# Codec.net
KiCad netlist of a schematic drawn in Altium Designer
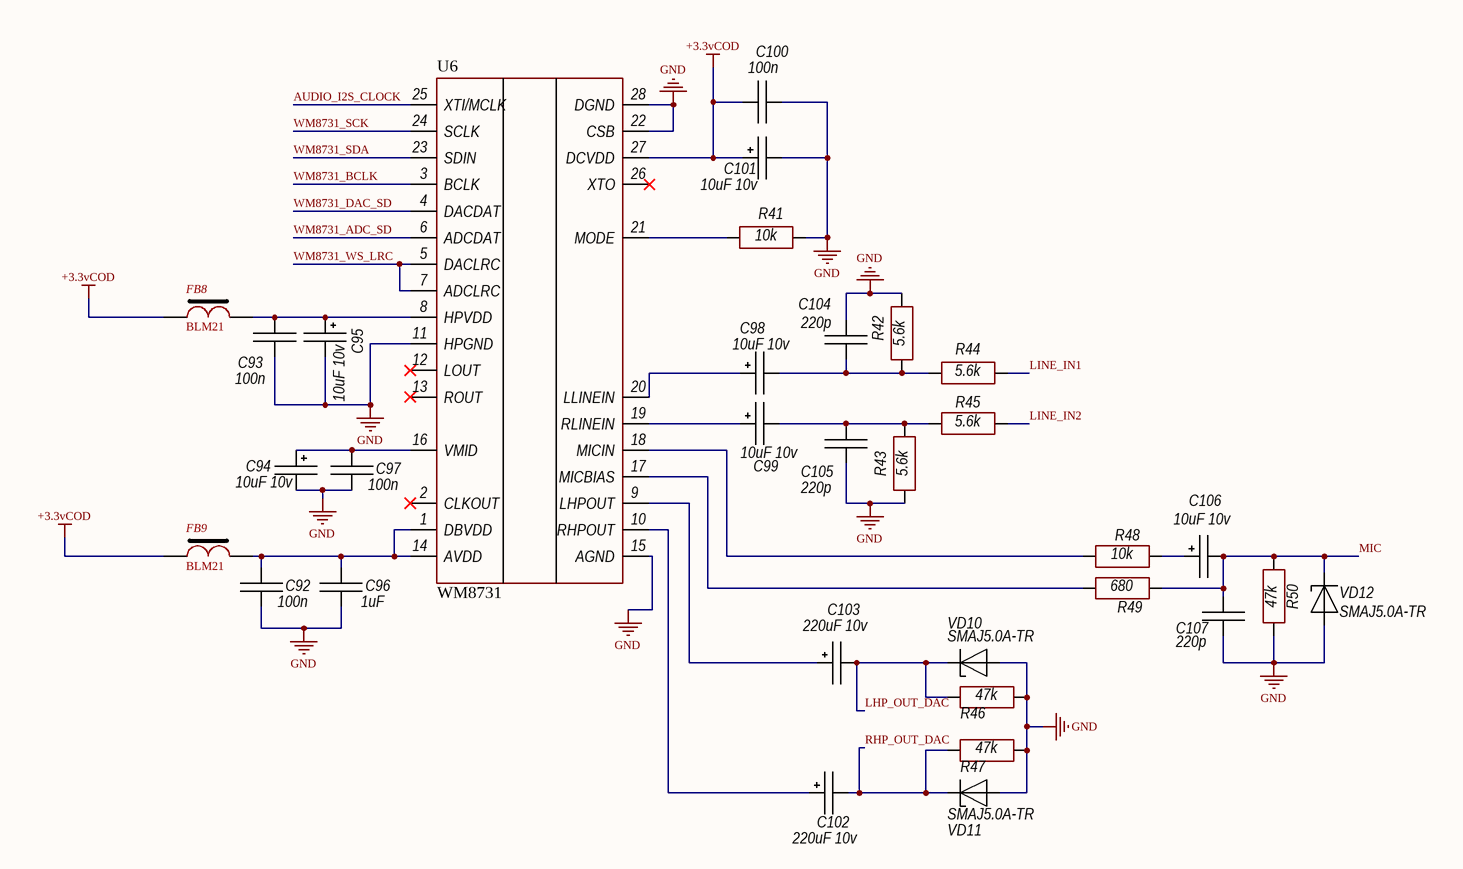
[diagram p0: Codec.SchDoc]

(export (version "E")
  (design (tool "Eeschema 10.0.6"))
  (components
    (comp (ref "C92")
      (value "100n")
      (footprint "standard:CH0805C")
      (libsource (lib "Discrete") (part "Capacitor"))
    )
    (comp (ref "C93")
      (value "100n")
      (footprint "standard:CH0805C")
      (libsource (lib "Discrete") (part "Capacitor"))
    )
    (comp (ref "C94")
      (value "10uF 10v")
      (footprint "standard:TANTAL_B")
      (libsource (lib "Discrete") (part "TantalCap"))
    )
    (comp (ref "C95")
      (value "10uF 10v")
      (footprint "standard:TANTAL_B")
      (libsource (lib "Discrete") (part "TantalCap"))
    )
    (comp (ref "C96")
      (value "1uF")
      (footprint "standard:CH0805C")
      (libsource (lib "Discrete") (part "Capacitor"))
    )
    (comp (ref "C97")
      (value "100n")
      (footprint "standard:CH0805C")
      (libsource (lib "Discrete") (part "Capacitor"))
    )
    (comp (ref "C98")
      (value "10uF 10v")
      (footprint "standard:TANTAL_B")
      (libsource (lib "Discrete") (part "TantalCap"))
    )
    (comp (ref "C99")
      (value "10uF 10v")
      (footprint "standard:TANTAL_B")
      (libsource (lib "Discrete") (part "TantalCap"))
    )
    (comp (ref "C100")
      (value "100n")
      (footprint "standard:CH0805C")
      (libsource (lib "Discrete") (part "Capacitor"))
    )
    (comp (ref "C101")
      (value "10uF 10v")
      (footprint "standard:TANTAL_B")
      (libsource (lib "Discrete") (part "TantalCap"))
    )
    (comp (ref "C102")
      (value "220uF 10v")
      (footprint "standard:TANTAL_D")
      (libsource (lib "Discrete") (part "TantalCap"))
    )
    (comp (ref "C103")
      (value "220uF 10v")
      (footprint "standard:TANTAL_D")
      (libsource (lib "Discrete") (part "TantalCap"))
    )
    (comp (ref "C104")
      (value "220p")
      (footprint "standard:CH0805C")
      (libsource (lib "Discrete") (part "Capacitor"))
    )
    (comp (ref "C105")
      (value "220p")
      (footprint "standard:CH0805C")
      (libsource (lib "Discrete") (part "Capacitor"))
    )
    (comp (ref "C106")
      (value "10uF 10v")
      (footprint "standard:TANTAL_B")
      (libsource (lib "Discrete") (part "TantalCap"))
    )
    (comp (ref "C107")
      (value "220p")
      (footprint "standard:CH0805C")
      (libsource (lib "Discrete") (part "Capacitor"))
    )
    (comp (ref "FB8") (value "BLM21") (footprint "CH0805L") (libsource (lib "Discrete") (part "FB-1")))
    (comp (ref "FB9") (value "BLM21") (footprint "CH0805L") (libsource (lib "Discrete") (part "FB-1")))
    (comp (ref "R41")
      (value "10k")
      (footprint "standard:CH0805R")
      (libsource (lib "Discrete") (part "Resistor"))
    )
    (comp (ref "R42") (value "5.6k") (footprint "standard:CH0805R") (libsource (lib "") (part "Resistor_1")))
    (comp (ref "R43") (value "5.6k") (footprint "standard:CH0805R") (libsource (lib "") (part "Resistor_1")))
    (comp (ref "R44") (value "5.6k") (footprint "standard:CH0805R") (libsource (lib "") (part "Resistor_2")))
    (comp (ref "R45") (value "5.6k") (footprint "standard:CH0805R") (libsource (lib "") (part "Resistor_2")))
    (comp (ref "R46")
      (value "47k")
      (footprint "standard:CH0805R")
      (libsource (lib "Discrete") (part "Resistor"))
    )
    (comp (ref "R47")
      (value "47k")
      (footprint "standard:CH0805R")
      (libsource (lib "Discrete") (part "Resistor"))
    )
    (comp (ref "R48")
      (value "10k")
      (footprint "standard:CH0805R")
      (libsource (lib "Discrete") (part "Resistor"))
    )
    (comp (ref "R49")
      (value "680")
      (footprint "standard:CH0805R")
      (libsource (lib "Discrete") (part "Resistor"))
    )
    (comp (ref "R50") (value "47k") (footprint "standard:CH0805R") (libsource (lib "") (part "Resistor_1")))
    (comp (ref "U6") (value "WM8731") (footprint "28-SSOP") (libsource (lib "Digital") (part "WM8731")))
    (comp (ref "VD10")
      (value "SMAJ5.0A-TR")
      (footprint "standard:SMA")
      (libsource (lib "Diods") (part "Diod Zener"))
    )
    (comp (ref "VD11")
      (value "SMAJ5.0A-TR")
      (footprint "standard:SMA")
      (libsource (lib "Diods") (part "Diod Zener"))
    )
    (comp (ref "VD12")
      (value "SMAJ5.0A-TR")
      (footprint "standard:SMA")
      (libsource (lib "Diods") (part "Diod Zener"))
    )
  )
  (nets
    (net (code "1") (name "+3.3vCOD") (class "Default")
      (node (ref "C100") (pin "1") (pinfunction "1_1") (pintype "power_in"))
      (node (ref "C101") (pin "1") (pinfunction "1_1") (pintype "power_in"))
      (node (ref "FB8") (pin "2") (pinfunction "2_2") (pintype "passive"))
      (node (ref "FB9") (pin "2") (pinfunction "2_2") (pintype "passive"))
      (node (ref "U6") (pin "27") (pinfunction "DCVDD_27") (pintype "passive"))
    )
    (net (code "2") (name "/AUDIO_I2S_CLOCK") (class "Default")
      (node (ref "U6") (pin "25") (pinfunction "XTI/MCLK_25") (pintype "passive"))
    )
    (net (code "3") (name "/LHP_OUT_DAC") (class "Default")
      (node (ref "C103") (pin "2") (pinfunction "2_2") (pintype "power_in"))
      (node (ref "R46") (pin "1") (pinfunction "1_1") (pintype "passive"))
      (node (ref "VD10") (pin "2") (pinfunction "C_2") (pintype "passive"))
    )
    (net (code "4") (name "/LINE_IN1") (class "Default")
      (node (ref "R44") (pin "2") (pinfunction "2_2") (pintype "passive"))
    )
    (net (code "5") (name "/LINE_IN2") (class "Default")
      (node (ref "R45") (pin "2") (pinfunction "2_2") (pintype "passive"))
    )
    (net (code "6") (name "/MIC") (class "Default")
      (node (ref "C106") (pin "2") (pinfunction "2_2") (pintype "power_in"))
      (node (ref "C107") (pin "1") (pinfunction "1_1") (pintype "power_in"))
      (node (ref "R49") (pin "2") (pinfunction "2_2") (pintype "passive"))
      (node (ref "R50") (pin "2") (pinfunction "2_2") (pintype "passive"))
      (node (ref "VD12") (pin "2") (pinfunction "C_2") (pintype "passive"))
    )
    (net (code "7") (name "/RHP_OUT_DAC") (class "Default")
      (node (ref "C102") (pin "2") (pinfunction "2_2") (pintype "power_in"))
      (node (ref "R47") (pin "1") (pinfunction "1_1") (pintype "passive"))
      (node (ref "VD11") (pin "2") (pinfunction "C_2") (pintype "passive"))
    )
    (net (code "8") (name "/WM8731_ADC_SD") (class "Default")
      (node (ref "U6") (pin "6") (pinfunction "ADCDAT_6") (pintype "passive"))
    )
    (net (code "9") (name "/WM8731_BCLK") (class "Default")
      (node (ref "U6") (pin "3") (pinfunction "BCLK_3") (pintype "passive"))
    )
    (net (code "10") (name "/WM8731_DAC_SD") (class "Default")
      (node (ref "U6") (pin "4") (pinfunction "DACDAT_4") (pintype "passive"))
    )
    (net (code "11") (name "/WM8731_SCK") (class "Default")
      (node (ref "U6") (pin "24") (pinfunction "SCLK_24") (pintype "passive"))
    )
    (net (code "12") (name "/WM8731_SDA") (class "Default")
      (node (ref "U6") (pin "23") (pinfunction "SDIN_23") (pintype "passive"))
    )
    (net (code "13") (name "/WM8731_WS_LRC") (class "Default")
      (node (ref "U6") (pin "5") (pinfunction "DACLRC_5") (pintype "passive"))
      (node (ref "U6") (pin "7") (pinfunction "ADCLRC_7") (pintype "passive"))
    )
    (net (code "14") (name "GND") (class "Default")
      (node (ref "C100") (pin "2") (pinfunction "2_2") (pintype "power_in"))
      (node (ref "C101") (pin "2") (pinfunction "2_2") (pintype "power_in"))
      (node (ref "C104") (pin "2") (pinfunction "2_2") (pintype "power_in"))
      (node (ref "C105") (pin "1") (pinfunction "1_1") (pintype "power_in"))
      (node (ref "C107") (pin "2") (pinfunction "2_2") (pintype "power_in"))
      (node (ref "C92") (pin "1") (pinfunction "1_1") (pintype "power_in"))
      (node (ref "C93") (pin "1") (pinfunction "1_1") (pintype "power_in"))
      (node (ref "C94") (pin "2") (pinfunction "2_2") (pintype "power_in"))
      (node (ref "C95") (pin "2") (pinfunction "2_2") (pintype "power_in"))
      (node (ref "C96") (pin "1") (pinfunction "1_1") (pintype "power_in"))
      (node (ref "C97") (pin "1") (pinfunction "1_1") (pintype "power_in"))
      (node (ref "R41") (pin "2") (pinfunction "2_2") (pintype "passive"))
      (node (ref "R42") (pin "2") (pinfunction "2_2") (pintype "passive"))
      (node (ref "R43") (pin "1") (pinfunction "1_1") (pintype "passive"))
      (node (ref "R46") (pin "2") (pinfunction "2_2") (pintype "passive"))
      (node (ref "R47") (pin "2") (pinfunction "2_2") (pintype "passive"))
      (node (ref "R50") (pin "1") (pinfunction "1_1") (pintype "passive"))
      (node (ref "U6") (pin "11") (pinfunction "HPGND_11") (pintype "passive"))
      (node (ref "U6") (pin "15") (pinfunction "AGND_15") (pintype "passive"))
      (node (ref "U6") (pin "22") (pinfunction "CSB_22") (pintype "passive"))
      (node (ref "U6") (pin "28") (pinfunction "DGND_28") (pintype "passive"))
      (node (ref "VD10") (pin "1") (pinfunction "A_1") (pintype "passive"))
      (node (ref "VD11") (pin "1") (pinfunction "A_1") (pintype "passive"))
      (node (ref "VD12") (pin "1") (pinfunction "A_1") (pintype "passive"))
    )
    (net (code "15") (name "Net-(C104-Pad1)") (class "Default")
      (node (ref "C104") (pin "1") (pinfunction "1_1") (pintype "power_in"))
      (node (ref "C98") (pin "2") (pinfunction "2_2") (pintype "power_in"))
      (node (ref "R42") (pin "1") (pinfunction "1_1") (pintype "passive"))
      (node (ref "R44") (pin "1") (pinfunction "1_1") (pintype "passive"))
    )
    (net (code "16") (name "Net-(C105-Pad2)") (class "Default")
      (node (ref "C105") (pin "2") (pinfunction "2_2") (pintype "power_in"))
      (node (ref "C99") (pin "2") (pinfunction "2_2") (pintype "power_in"))
      (node (ref "R43") (pin "2") (pinfunction "2_2") (pintype "passive"))
      (node (ref "R45") (pin "1") (pinfunction "1_1") (pintype "passive"))
    )
    (net (code "17") (name "Net-(C106-Pad1)") (class "Default")
      (node (ref "C106") (pin "1") (pinfunction "1_1") (pintype "power_in"))
      (node (ref "R48") (pin "2") (pinfunction "2_2") (pintype "passive"))
    )
    (net (code "18") (name "Net-(U6-AVDD)") (class "Default")
      (node (ref "C92") (pin "2") (pinfunction "2_2") (pintype "power_in"))
      (node (ref "C96") (pin "2") (pinfunction "2_2") (pintype "power_in"))
      (node (ref "FB9") (pin "1") (pinfunction "1_1") (pintype "passive"))
      (node (ref "U6") (pin "1") (pinfunction "DBVDD_1") (pintype "passive"))
      (node (ref "U6") (pin "14") (pinfunction "AVDD_14") (pintype "passive"))
    )
    (net (code "19") (name "Net-(U6-HPVDD)") (class "Default")
      (node (ref "C93") (pin "2") (pinfunction "2_2") (pintype "power_in"))
      (node (ref "C95") (pin "1") (pinfunction "1_1") (pintype "power_in"))
      (node (ref "FB8") (pin "1") (pinfunction "1_1") (pintype "passive"))
      (node (ref "U6") (pin "8") (pinfunction "HPVDD_8") (pintype "passive"))
    )
    (net (code "20") (name "Net-(U6-LHPOUT)") (class "Default")
      (node (ref "C103") (pin "1") (pinfunction "1_1") (pintype "power_in"))
      (node (ref "U6") (pin "9") (pinfunction "LHPOUT_9") (pintype "passive"))
    )
    (net (code "21") (name "Net-(U6-LLINEIN)") (class "Default")
      (node (ref "C98") (pin "1") (pinfunction "1_1") (pintype "power_in"))
      (node (ref "U6") (pin "20") (pinfunction "LLINEIN_20") (pintype "passive"))
    )
    (net (code "22") (name "Net-(U6-MICBIAS)") (class "Default")
      (node (ref "R49") (pin "1") (pinfunction "1_1") (pintype "passive"))
      (node (ref "U6") (pin "17") (pinfunction "MICBIAS_17") (pintype "passive"))
    )
    (net (code "23") (name "Net-(U6-MICIN)") (class "Default")
      (node (ref "R48") (pin "1") (pinfunction "1_1") (pintype "passive"))
      (node (ref "U6") (pin "18") (pinfunction "MICIN_18") (pintype "passive"))
    )
    (net (code "24") (name "Net-(U6-MODE)") (class "Default")
      (node (ref "R41") (pin "1") (pinfunction "1_1") (pintype "passive"))
      (node (ref "U6") (pin "21") (pinfunction "MODE_21") (pintype "passive"))
    )
    (net (code "25") (name "Net-(U6-RHPOUT)") (class "Default")
      (node (ref "C102") (pin "1") (pinfunction "1_1") (pintype "power_in"))
      (node (ref "U6") (pin "10") (pinfunction "RHPOUT_10") (pintype "passive"))
    )
    (net (code "26") (name "Net-(U6-RLINEIN)") (class "Default")
      (node (ref "C99") (pin "1") (pinfunction "1_1") (pintype "power_in"))
      (node (ref "U6") (pin "19") (pinfunction "RLINEIN_19") (pintype "passive"))
    )
    (net (code "27") (name "Net-(U6-VMID)") (class "Default")
      (node (ref "C94") (pin "1") (pinfunction "1_1") (pintype "power_in"))
      (node (ref "C97") (pin "2") (pinfunction "2_2") (pintype "power_in"))
      (node (ref "U6") (pin "16") (pinfunction "VMID_16") (pintype "passive"))
    )
    (net (code "28") (name "unconnected-(U6-CLKOUT-Pad2)") (class "Default")
      (node (ref "U6") (pin "2") (pinfunction "CLKOUT_2") (pintype "passive+no_connect"))
    )
    (net (code "29") (name "unconnected-(U6-LOUT-Pad12)") (class "Default")
      (node (ref "U6") (pin "12") (pinfunction "LOUT_12") (pintype "passive+no_connect"))
    )
    (net (code "30") (name "unconnected-(U6-ROUT-Pad13)") (class "Default")
      (node (ref "U6") (pin "13") (pinfunction "ROUT_13") (pintype "passive+no_connect"))
    )
    (net (code "31") (name "unconnected-(U6-XTO-Pad26)") (class "Default")
      (node (ref "U6") (pin "26") (pinfunction "XTO_26") (pintype "passive+no_connect"))
    )
  )
)
